# Deckelplatine_v092.net
KiCad netlist of a schematic drawn in EAGLE
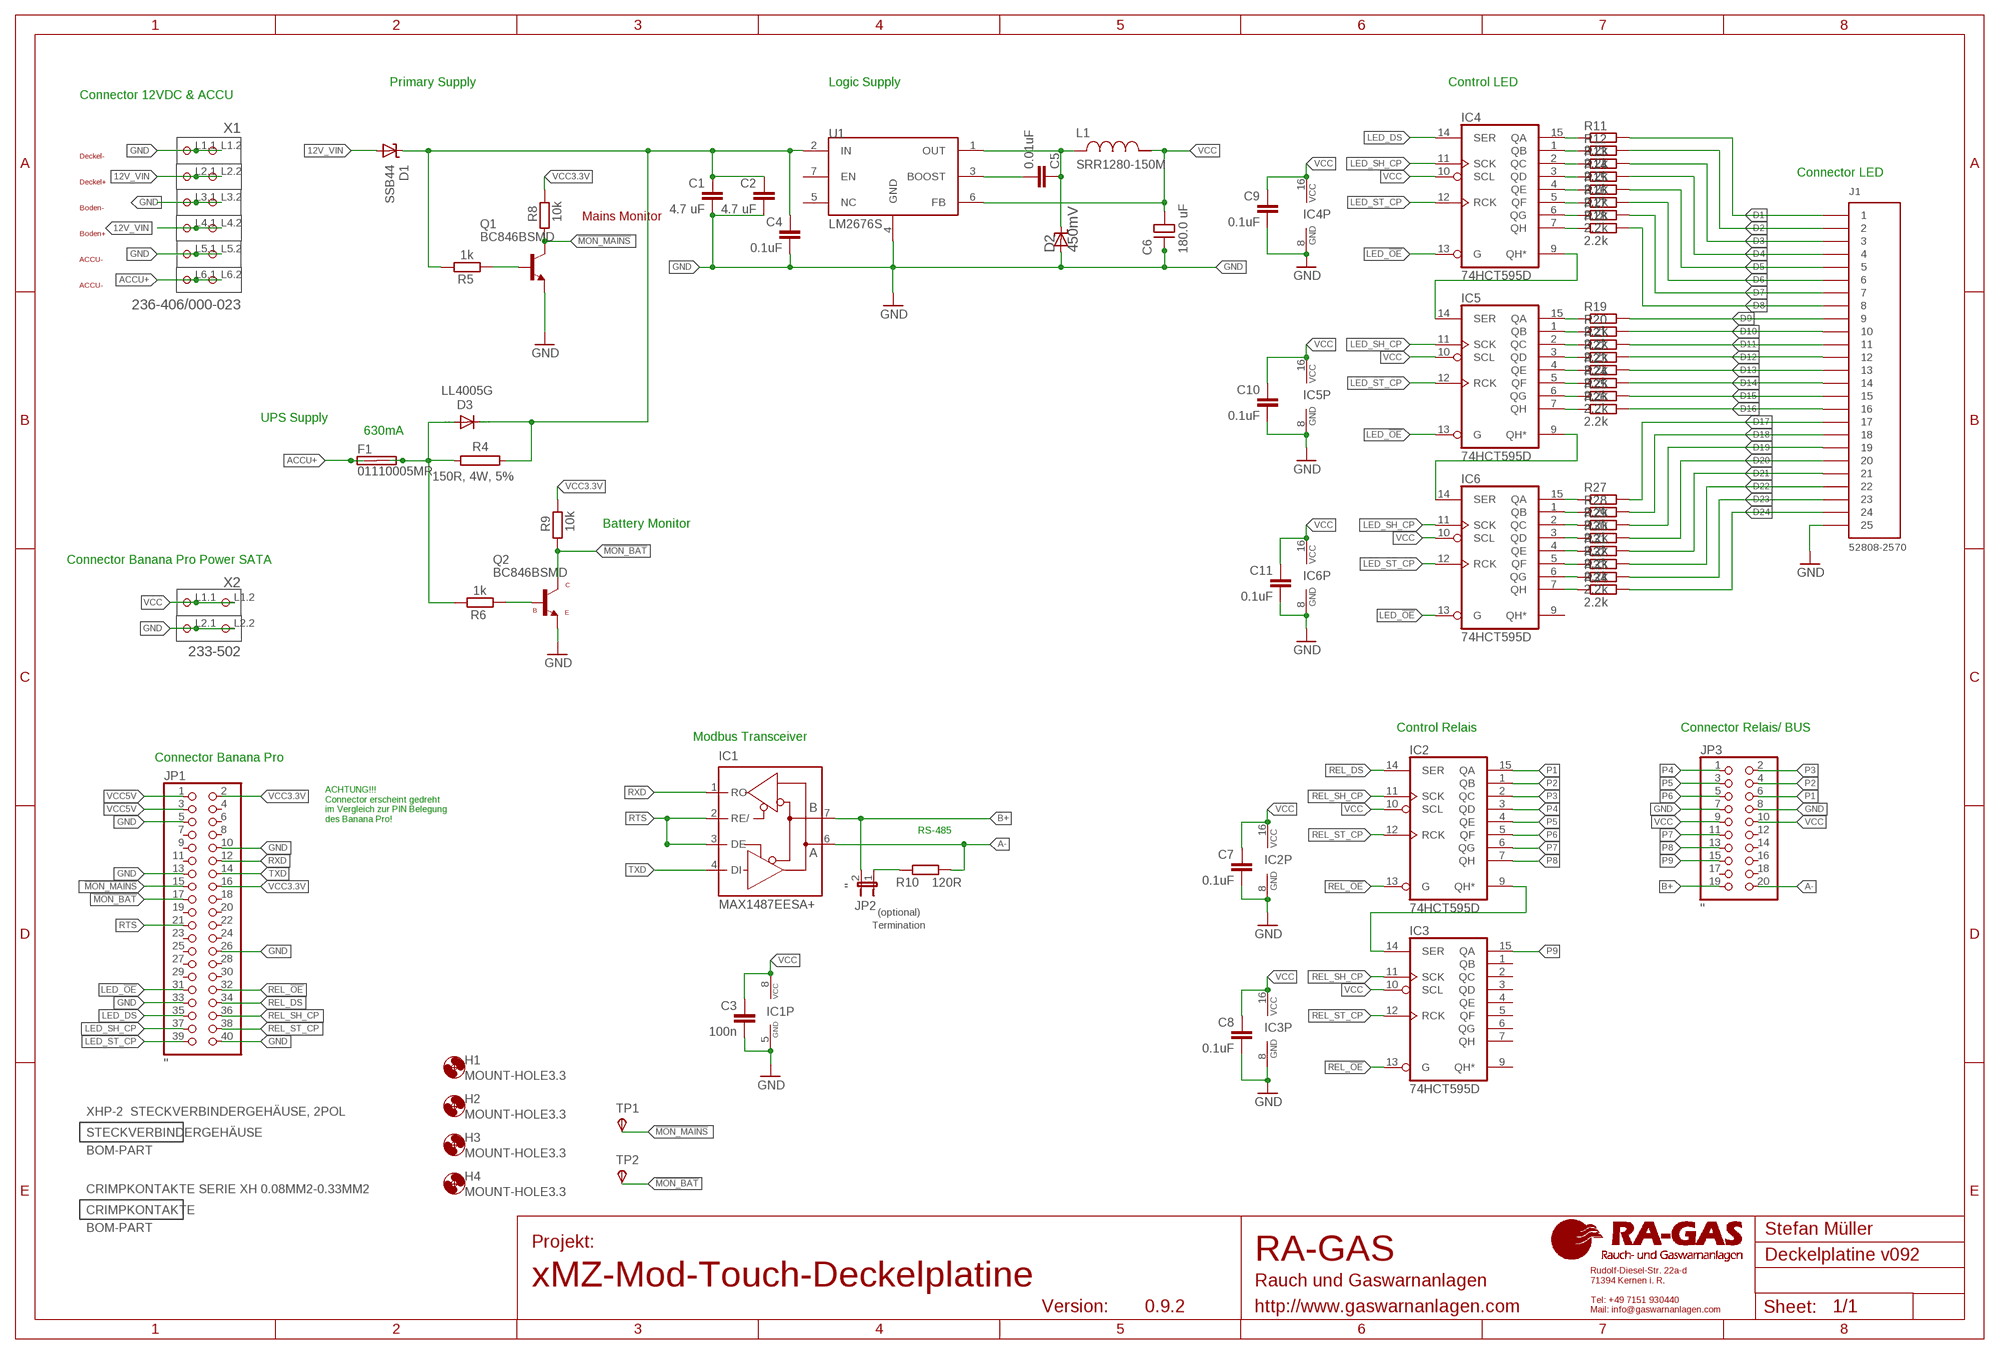
[diagram p0: schematic, sheet 1]

(export (version "E")
  (design (tool "Eeschema 10.0.6"))
  (components
    (comp (ref "C1")
      (value "4.7 uF")
      (footprint "eagle-import:GRM21BR61E475MA12L")
      (fields (field (name "MANUFACTURER_PART_NUMBER") "GRM21BR61E475MA12L") (field (name "MF") "MURATA"))
      (libsource (lib "eagle-import") (part "GRM21BR61E475MA12L"))
    )
    (comp (ref "C2")
      (value "4.7 uF")
      (footprint "eagle-import:GRM21BR61E475MA12L")
      (fields (field (name "MANUFACTURER_PART_NUMBER") "GRM21BR61E475MA12L") (field (name "MF") "MURATA"))
      (libsource (lib "eagle-import") (part "GRM21BR61E475MA12L"))
    )
    (comp (ref "C3")
      (value "100n")
      (footprint "eagle-import:C0603")
      (fields
        (field (name "MF") "KEMET")
        (field (name "MPN") "C0603C104K8RACTU")
        (field (name "PARTNO") "ECHU-16-100N")
      )
      (libsource (lib "eagle-import") (part "C-EUC0603"))
    )
    (comp (ref "C4")
      (value "0.1uF")
      (footprint "eagle-import:0805")
      (fields (field (name "MANUFACTURER_PART_NUMBER") "08053C104KAT2A") (field (name "MF") "AVX"))
      (libsource (lib "eagle-import") (part "08053C104KAT2A"))
    )
    (comp (ref "C5")
      (value "0.01uF")
      (footprint "eagle-import:GRM216R71H103KA01D")
      (fields (field (name "MANUFACTURER_PART_NUMBER") "GRM216R71H103KA01D") (field (name "MF") "MURATA"))
      (libsource (lib "eagle-import") (part "GRM216R71H103KA01D"))
    )
    (comp (ref "C6")
      (value "180.0 uF")
      (footprint "eagle-import:SM_RADIAL_10MM")
      (fields
        (field (name "MF") "PANASONIC ELECTRONIC COMPONENTS")
        (field (name "MPN") "16SVP180MX")
        (field (name "PARTNO") "RAD FC 560/35")
      )
      (libsource (lib "eagle-import") (part "16SVP180MSM_RADIAL_10MM"))
    )
    (comp (ref "C7")
      (value "0.1uF")
      (footprint "eagle-import:C0603")
      (fields
        (field (name "MF") "KEMET")
        (field (name "MPN") "C0603C104K8RACTU")
        (field (name "PARTNO") "SMD TAN.0,1/35")
      )
      (libsource (lib "eagle-import") (part "C-EUC0603"))
    )
    (comp (ref "C8")
      (value "0.1uF")
      (footprint "eagle-import:C0603")
      (fields
        (field (name "MF") "KEMET")
        (field (name "MPN") "C0603C104K8RACTU")
        (field (name "PARTNO") "SMD TAN.0,1/35")
      )
      (libsource (lib "eagle-import") (part "C-EUC0603"))
    )
    (comp (ref "C9")
      (value "0.1uF")
      (footprint "eagle-import:C0603")
      (fields
        (field (name "MF") "KEMET")
        (field (name "MPN") "C0603C104K8RACTU")
        (field (name "PARTNO") "SMD TAN.0,1/35")
      )
      (libsource (lib "eagle-import") (part "C-EUC0603"))
    )
    (comp (ref "C10")
      (value "0.1uF")
      (footprint "eagle-import:C0603")
      (fields
        (field (name "MF") "KEMET")
        (field (name "MPN") "C0603C104K8RACTU")
        (field (name "PARTNO") "SMD TAN.0,1/35")
      )
      (libsource (lib "eagle-import") (part "C-EUC0603"))
    )
    (comp (ref "C11")
      (value "0.1uF")
      (footprint "eagle-import:C0603")
      (fields
        (field (name "MF") "KEMET")
        (field (name "MPN") "C0603C104K8RACTU")
        (field (name "PARTNO") "SMD TAN.0,1/35")
      )
      (libsource (lib "eagle-import") (part "C-EUC0603"))
    )
    (comp (ref "D1")
      (value "SSB44")
      (footprint "eagle-import:SMBJ")
      (fields (field (name "MF") "VISHAY") (field (name "MPN") "SSB44-E3/52T"))
      (libsource (lib "eagle-import") (part "SUPPRESSOR-SMBJ"))
    )
    (comp (ref "D2")
      (value "450mV")
      (footprint "eagle-import:SMB")
      (fields (field (name "MANUFACTURER_PART_NUMBER") "B340LB-13-F") (field (name "MF") "DIODES INC."))
      (libsource (lib "eagle-import") (part "B340LB-13-F"))
    )
    (comp (ref "D3")
      (value "LL4005G")
      (footprint "eagle-import:MELF-MLL41")
      (fields (field (name "MF") "TAIWAN SEMICONDUCTOR"))
      (libsource (lib "eagle-import") (part "DIODE-MELF-MLL41"))
    )
    (comp (ref "F1")
      (value "01110005MR")
      (footprint "eagle-import:01110005MR")
      (fields (field (name "MF") "LITTELFUSE"))
      (libsource (lib "eagle-import") (part "01110005MR"))
    )
    (comp (ref "H1")
      (value "MOUNT-HOLE3.3")
      (footprint "eagle-import:3,3")
      (libsource (lib "eagle-import") (part "MOUNT-HOLE3.3"))
    )
    (comp (ref "H2")
      (value "MOUNT-HOLE3.3")
      (footprint "eagle-import:3,3")
      (libsource (lib "eagle-import") (part "MOUNT-HOLE3.3"))
    )
    (comp (ref "H3")
      (value "MOUNT-HOLE3.3")
      (footprint "eagle-import:3,3")
      (libsource (lib "eagle-import") (part "MOUNT-HOLE3.3"))
    )
    (comp (ref "H4")
      (value "MOUNT-HOLE3.3")
      (footprint "eagle-import:3,3")
      (libsource (lib "eagle-import") (part "MOUNT-HOLE3.3"))
    )
    (comp (ref "IC1")
      (value "MAX1487EESA+")
      (footprint "eagle-import:SO08")
      (fields
        (field (name "MF") "MAXIM")
        (field (name "MPN") "MAX481CSA")
        (field (name "MF_1") "MAXIM INTEGRATED PRODUCTS")
        (field (name "MPN_1") "MAX1487EESA+")
        (field (name "OC_FARNELL") "1593310")
        (field (name "PARTNO") "MAX481CSA")
      )
      (libsource (lib "eagle-import") (part "MAX481CSA"))
    )
    (comp (ref "IC2")
      (value "74HCT595D")
      (footprint "eagle-import:SO16")
      (fields
        (field (name "MF") "NXP")
        (field (name "MPN") "74HCT595D")
        (field (name "OC_FARNELL") "2098004")
        (field (name "PARTNO") "SMD HC 595")
      )
      (libsource (lib "eagle-import") (part "74595DHCT"))
    )
    (comp (ref "IC3")
      (value "74HCT595D")
      (footprint "eagle-import:SO16")
      (fields
        (field (name "MF") "NXP")
        (field (name "MPN") "74HCT595D")
        (field (name "OC_FARNELL") "2098004")
        (field (name "PARTNO") "SMD HC 595")
      )
      (libsource (lib "eagle-import") (part "74595DHCT"))
    )
    (comp (ref "IC4")
      (value "74HCT595D")
      (footprint "eagle-import:SO16")
      (fields
        (field (name "MF") "NXP")
        (field (name "MPN") "74HCT595D")
        (field (name "OC_FARNELL") "2098004")
        (field (name "PARTNO") "SMD HC 595")
      )
      (libsource (lib "eagle-import") (part "74595DHCT"))
    )
    (comp (ref "IC5")
      (value "74HCT595D")
      (footprint "eagle-import:SO16")
      (fields
        (field (name "MF") "NXP")
        (field (name "MPN") "74HCT595D")
        (field (name "OC_FARNELL") "2098004")
        (field (name "PARTNO") "SMD HC 595")
      )
      (libsource (lib "eagle-import") (part "74595DHCT"))
    )
    (comp (ref "IC6")
      (value "74HCT595D")
      (footprint "eagle-import:SO16")
      (fields
        (field (name "MF") "NXP")
        (field (name "MPN") "74HCT595D")
        (field (name "OC_FARNELL") "2098004")
        (field (name "PARTNO") "SMD HC 595")
      )
      (libsource (lib "eagle-import") (part "74595DHCT"))
    )
    (comp (ref "J1")
      (value "52808-2570")
      (footprint "eagle-import:52808-2570")
      (fields (field (name "MF") "MOLEX"))
      (libsource (lib "eagle-import") (part "52808-2570"))
    )
    (comp (ref "JP1")
      (value "''")
      (footprint "eagle-import:2X20")
      (fields (field (name "MF") "HARWIN") (field (name "MPN") "M20-6112045"))
      (libsource (lib "eagle-import") (part "PINHD-2X20"))
    )
    (comp (ref "JP2")
      (value "''")
      (footprint "eagle-import:JP1")
      (fields (field (name "MF") "TE CONNECTIVITY / AMP") (field (name "MPN") "825433-2"))
      (libsource (lib "eagle-import") (part "JP1E"))
    )
    (comp (ref "JP3")
      (value "''")
      (footprint "eagle-import:2X10")
      (fields (field (name "MF") "TE CONNECTIVITY / AMP") (field (name "MPN") "5103308-5"))
      (libsource (lib "eagle-import") (part "PINHD-2X10"))
    )
    (comp (ref "L1")
      (value "SRR1280-150M")
      (footprint "eagle-import:SRR1280")
      (fields (field (name "MF") "COILCRAFT") (field (name "MPN") "MSS1278-153MLD"))
      (libsource (lib "eagle-import") (part "SRR1280-150M"))
    )
    (comp (ref "Q1")
      (value "BC846BSMD")
      (footprint "eagle-import:SOT23")
      (fields (field (name "MF") "NXP") (field (name "MPN") "BC846,215"))
      (libsource (lib "eagle-import") (part "BC846SMDB"))
    )
    (comp (ref "Q2")
      (value "BC846BSMD")
      (footprint "eagle-import:SOT23")
      (fields (field (name "MF") "NXP") (field (name "MPN") "BC846,215"))
      (libsource (lib "eagle-import") (part "BC846SMDB"))
    )
    (comp (ref "R4")
      (value "150R, 4W, 5%")
      (footprint "eagle-import:KH206-8")
      (fields
        (field (name "MF") "TE CONNECTIVITY / CGS")
        (field (name "MPN") "ER74150RJT")
        (field (name "OC_FARNELL") "1751842")
      )
      (libsource (lib "eagle-import") (part "RKH206-8"))
    )
    (comp (ref "R5")
      (value "1k")
      (footprint "eagle-import:R1210")
      (fields (field (name "MF") "PANASONIC ELECTRONIC COMPONENTS") (field (name "MPN") "ERJP14F1001U"))
      (libsource (lib "eagle-import") (part "rcl_R-EU_R1210"))
    )
    (comp (ref "R6")
      (value "1k")
      (footprint "eagle-import:R1210")
      (fields (field (name "MF") "PANASONIC ELECTRONIC COMPONENTS") (field (name "MPN") "ERJP14F1001U"))
      (libsource (lib "eagle-import") (part "rcl_R-EU_R1210"))
    )
    (comp (ref "R8")
      (value "10k")
      (footprint "eagle-import:R1210")
      (fields (field (name "MF") "PANASONIC ELECTRONIC COMPONENTS") (field (name "MPN") "ERJP14F1002U"))
      (libsource (lib "eagle-import") (part "rcl_R-EU_R1210"))
    )
    (comp (ref "R9")
      (value "10k")
      (footprint "eagle-import:R1210")
      (fields (field (name "MF") "PANASONIC ELECTRONIC COMPONENTS") (field (name "MPN") "ERJP14F1002U"))
      (libsource (lib "eagle-import") (part "rcl_R-EU_R1210"))
    )
    (comp (ref "R10")
      (value "120R")
      (footprint "eagle-import:R1206")
      (fields (field (name "MF") "TE CONNECTIVITY") (field (name "MPN") "CRGH1206F120R"))
      (libsource (lib "eagle-import") (part "rcl_R-EU_R1206"))
    )
    (comp (ref "R11")
      (value "2.2k")
      (footprint "eagle-import:R0603")
      (fields
        (field (name "MF") "YAGEO (PHYCOMP)")
        (field (name "MPN") "RC0603FR-072K2L")
        (field (name "PARTNO") "SMD-0603 2,2K")
      )
      (libsource (lib "eagle-import") (part "R-EU_R0603"))
    )
    (comp (ref "R12")
      (value "2.2k")
      (footprint "eagle-import:R0603")
      (fields
        (field (name "MF") "YAGEO (PHYCOMP)")
        (field (name "MPN") "RC0603FR-072K2L")
        (field (name "PARTNO") "SMD-0603 2,2K")
      )
      (libsource (lib "eagle-import") (part "R-EU_R0603"))
    )
    (comp (ref "R13")
      (value "2.2k")
      (footprint "eagle-import:R0603")
      (fields
        (field (name "MF") "YAGEO (PHYCOMP)")
        (field (name "MPN") "RC0603FR-072K2L")
        (field (name "PARTNO") "SMD-0603 2,2K")
      )
      (libsource (lib "eagle-import") (part "R-EU_R0603"))
    )
    (comp (ref "R14")
      (value "2.2k")
      (footprint "eagle-import:R0603")
      (fields
        (field (name "MF") "YAGEO (PHYCOMP)")
        (field (name "MPN") "RC0603FR-072K2L")
        (field (name "PARTNO") "SMD-0603 2,2K")
      )
      (libsource (lib "eagle-import") (part "R-EU_R0603"))
    )
    (comp (ref "R15")
      (value "2.2k")
      (footprint "eagle-import:R0603")
      (fields
        (field (name "MF") "YAGEO (PHYCOMP)")
        (field (name "MPN") "RC0603FR-072K2L")
        (field (name "PARTNO") "SMD-0603 2,2K")
      )
      (libsource (lib "eagle-import") (part "R-EU_R0603"))
    )
    (comp (ref "R16")
      (value "2.2k")
      (footprint "eagle-import:R0603")
      (fields
        (field (name "MF") "YAGEO (PHYCOMP)")
        (field (name "MPN") "RC0603FR-072K2L")
        (field (name "PARTNO") "SMD-0603 2,2K")
      )
      (libsource (lib "eagle-import") (part "R-EU_R0603"))
    )
    (comp (ref "R17")
      (value "2.2k")
      (footprint "eagle-import:R0603")
      (fields
        (field (name "MF") "YAGEO (PHYCOMP)")
        (field (name "MPN") "RC0603FR-072K2L")
        (field (name "PARTNO") "SMD-0603 2,2K")
      )
      (libsource (lib "eagle-import") (part "R-EU_R0603"))
    )
    (comp (ref "R18")
      (value "2.2k")
      (footprint "eagle-import:R0603")
      (fields
        (field (name "MF") "YAGEO (PHYCOMP)")
        (field (name "MPN") "RC0603FR-072K2L")
        (field (name "PARTNO") "SMD-0603 2,2K")
      )
      (libsource (lib "eagle-import") (part "R-EU_R0603"))
    )
    (comp (ref "R19")
      (value "2.2k")
      (footprint "eagle-import:R0603")
      (fields
        (field (name "MF") "YAGEO (PHYCOMP)")
        (field (name "MPN") "RC0603FR-072K2L")
        (field (name "PARTNO") "SMD-0603 2,2K")
      )
      (libsource (lib "eagle-import") (part "R-EU_R0603"))
    )
    (comp (ref "R20")
      (value "2.2k")
      (footprint "eagle-import:R0603")
      (fields
        (field (name "MF") "YAGEO (PHYCOMP)")
        (field (name "MPN") "RC0603FR-072K2L")
        (field (name "PARTNO") "SMD-0603 2,2K")
      )
      (libsource (lib "eagle-import") (part "R-EU_R0603"))
    )
    (comp (ref "R21")
      (value "2.2k")
      (footprint "eagle-import:R0603")
      (fields
        (field (name "MF") "YAGEO (PHYCOMP)")
        (field (name "MPN") "RC0603FR-072K2L")
        (field (name "PARTNO") "SMD-0603 2,2K")
      )
      (libsource (lib "eagle-import") (part "R-EU_R0603"))
    )
    (comp (ref "R22")
      (value "2.2k")
      (footprint "eagle-import:R0603")
      (fields
        (field (name "MF") "YAGEO (PHYCOMP)")
        (field (name "MPN") "RC0603FR-072K2L")
        (field (name "PARTNO") "SMD-0603 2,2K")
      )
      (libsource (lib "eagle-import") (part "R-EU_R0603"))
    )
    (comp (ref "R23")
      (value "2.2k")
      (footprint "eagle-import:R0603")
      (fields
        (field (name "MF") "YAGEO (PHYCOMP)")
        (field (name "MPN") "RC0603FR-072K2L")
        (field (name "PARTNO") "SMD-0603 2,2K")
      )
      (libsource (lib "eagle-import") (part "R-EU_R0603"))
    )
    (comp (ref "R24")
      (value "2.2k")
      (footprint "eagle-import:R0603")
      (fields
        (field (name "MF") "YAGEO (PHYCOMP)")
        (field (name "MPN") "RC0603FR-072K2L")
        (field (name "PARTNO") "SMD-0603 2,2K")
      )
      (libsource (lib "eagle-import") (part "R-EU_R0603"))
    )
    (comp (ref "R25")
      (value "2.2k")
      (footprint "eagle-import:R0603")
      (fields
        (field (name "MF") "YAGEO (PHYCOMP)")
        (field (name "MPN") "RC0603FR-072K2L")
        (field (name "PARTNO") "SMD-0603 2,2K")
      )
      (libsource (lib "eagle-import") (part "R-EU_R0603"))
    )
    (comp (ref "R26")
      (value "2.2k")
      (footprint "eagle-import:R0603")
      (fields
        (field (name "MF") "YAGEO (PHYCOMP)")
        (field (name "MPN") "RC0603FR-072K2L")
        (field (name "PARTNO") "SMD-0603 2,2K")
      )
      (libsource (lib "eagle-import") (part "R-EU_R0603"))
    )
    (comp (ref "R27")
      (value "2.2k")
      (footprint "eagle-import:R0603")
      (fields
        (field (name "MF") "YAGEO (PHYCOMP)")
        (field (name "MPN") "RC0603FR-072K2L")
        (field (name "PARTNO") "SMD-0603 2,2K")
      )
      (libsource (lib "eagle-import") (part "R-EU_R0603"))
    )
    (comp (ref "R28")
      (value "2.2k")
      (footprint "eagle-import:R0603")
      (fields
        (field (name "MF") "YAGEO (PHYCOMP)")
        (field (name "MPN") "RC0603FR-072K2L")
        (field (name "PARTNO") "SMD-0603 2,2K")
      )
      (libsource (lib "eagle-import") (part "R-EU_R0603"))
    )
    (comp (ref "R29")
      (value "2.2k")
      (footprint "eagle-import:R0603")
      (fields
        (field (name "MF") "YAGEO (PHYCOMP)")
        (field (name "MPN") "RC0603FR-072K2L")
        (field (name "PARTNO") "SMD-0603 2,2K")
      )
      (libsource (lib "eagle-import") (part "R-EU_R0603"))
    )
    (comp (ref "R30")
      (value "2.2k")
      (footprint "eagle-import:R0603")
      (fields
        (field (name "MF") "YAGEO (PHYCOMP)")
        (field (name "MPN") "RC0603FR-072K2L")
        (field (name "PARTNO") "SMD-0603 2,2K")
      )
      (libsource (lib "eagle-import") (part "R-EU_R0603"))
    )
    (comp (ref "R31")
      (value "2.2k")
      (footprint "eagle-import:R0603")
      (fields
        (field (name "MF") "YAGEO (PHYCOMP)")
        (field (name "MPN") "RC0603FR-072K2L")
        (field (name "PARTNO") "SMD-0603 2,2K")
      )
      (libsource (lib "eagle-import") (part "R-EU_R0603"))
    )
    (comp (ref "R32")
      (value "2.2k")
      (footprint "eagle-import:R0603")
      (fields
        (field (name "MF") "YAGEO (PHYCOMP)")
        (field (name "MPN") "RC0603FR-072K2L")
        (field (name "PARTNO") "SMD-0603 2,2K")
      )
      (libsource (lib "eagle-import") (part "R-EU_R0603"))
    )
    (comp (ref "R33")
      (value "2.2k")
      (footprint "eagle-import:R0603")
      (fields
        (field (name "MF") "YAGEO (PHYCOMP)")
        (field (name "MPN") "RC0603FR-072K2L")
        (field (name "PARTNO") "SMD-0603 2,2K")
      )
      (libsource (lib "eagle-import") (part "R-EU_R0603"))
    )
    (comp (ref "R34")
      (value "2.2k")
      (footprint "eagle-import:R0603")
      (fields
        (field (name "MF") "YAGEO (PHYCOMP)")
        (field (name "MPN") "RC0603FR-072K2L")
        (field (name "PARTNO") "SMD-0603 2,2K")
      )
      (libsource (lib "eagle-import") (part "R-EU_R0603"))
    )
    (comp (ref "TP1")
      (value "TPSB1,27")
      (footprint "eagle-import:B1,27")
      (libsource (lib "eagle-import") (part "TPSB1,27"))
    )
    (comp (ref "TP2")
      (value "TPSB1,27")
      (footprint "eagle-import:B1,27")
      (libsource (lib "eagle-import") (part "TPSB1,27"))
    )
    (comp (ref "U1")
      (value "LM2676S")
      (footprint "eagle-import:TO-263-7")
      (fields (field (name "MF") "TEXAS INSTRUMENTS") (field (name "MPN") "LM2676S-5.0/NOPB"))
      (libsource (lib "eagle-import") (part "LM2676S"))
    )
    (comp (ref "X1")
      (value "236-406/000-023")
      (footprint "eagle-import:P-236-406")
      (fields (field (name "MF") "WAGO") (field (name "MPN") "236-406"))
      (libsource (lib "eagle-import") (part "236-406/000-023"))
    )
    (comp (ref "X2")
      (value "233-502")
      (footprint "eagle-import:P-233-502")
      (fields (field (name "MF") "WAGO") (field (name "MPN") "233-502."))
      (libsource (lib "eagle-import") (part "233-502"))
    )
  )
  (nets
    (net (code "1") (name "/LED_~{OE}") (class "Default")
      (node (ref "IC4") (pin "13") (pinfunction "G_13") (pintype "input"))
      (node (ref "IC5") (pin "13") (pinfunction "G_13") (pintype "input"))
      (node (ref "IC6") (pin "13") (pinfunction "G_13") (pintype "input"))
      (node (ref "JP1") (pin "31") (pinfunction "31_31") (pintype "passive"))
    )
    (net (code "2") (name "/REL_~{OE}") (class "Default")
      (node (ref "IC2") (pin "13") (pinfunction "G_13") (pintype "input"))
      (node (ref "IC3") (pin "13") (pinfunction "G_13") (pintype "input"))
      (node (ref "JP1") (pin "32") (pinfunction "32_32") (pintype "passive"))
    )
    (net (code "3") (name "/~{MON_BAT}") (class "Default")
      (node (ref "JP1") (pin "17") (pinfunction "17_17") (pintype "passive"))
      (node (ref "Q2") (pin "3") (pinfunction "C_3") (pintype "passive"))
      (node (ref "R9") (pin "1") (pinfunction "1_1") (pintype "passive"))
      (node (ref "TP2") (pin "TP") (pinfunction "PP_TP") (pintype "input"))
    )
    (net (code "4") (name "/~{MON_MAINS}") (class "Default")
      (node (ref "JP1") (pin "15") (pinfunction "15_15") (pintype "passive"))
      (node (ref "Q1") (pin "3") (pinfunction "C_3") (pintype "passive"))
      (node (ref "R8") (pin "1") (pinfunction "1_1") (pintype "passive"))
      (node (ref "TP1") (pin "TP") (pinfunction "PP_TP") (pintype "input"))
    )
    (net (code "5") (name "12V_VIN") (class "Default")
      (node (ref "C1") (pin "1") (pinfunction "1_1") (pintype "passive"))
      (node (ref "C2") (pin "1") (pinfunction "1_1") (pintype "passive"))
      (node (ref "C4") (pin "1") (pinfunction "1_1") (pintype "passive"))
      (node (ref "D1") (pin "A") (pinfunction "A_A") (pintype "passive"))
      (node (ref "D1") (pin "C") (pinfunction "C_C") (pintype "passive"))
      (node (ref "D3") (pin "C") (pinfunction "C_C") (pintype "passive"))
      (node (ref "R4") (pin "2") (pinfunction "2_2") (pintype "passive"))
      (node (ref "R5") (pin "2") (pinfunction "2_2") (pintype "passive"))
      (node (ref "U1") (pin "2") (pinfunction "IN_2") (pintype "power_in"))
      (node (ref "X1") (pin "L2.1") (pinfunction "P2.1_L2.1") (pintype "bidirectional"))
      (node (ref "X1") (pin "L2.2") (pinfunction "P2.2_L2.2") (pintype "bidirectional"))
      (node (ref "X1") (pin "L4.1") (pinfunction "P4.1_L4.1") (pintype "bidirectional"))
      (node (ref "X1") (pin "L4.2") (pinfunction "P4.2_L4.2") (pintype "bidirectional"))
    )
    (net (code "6") (name "A-") (class "Default")
      (node (ref "IC1") (pin "6") (pinfunction "A_6") (pintype "passive"))
      (node (ref "JP3") (pin "20") (pinfunction "20_20") (pintype "passive"))
      (node (ref "R10") (pin "2") (pinfunction "2_2") (pintype "passive"))
    )
    (net (code "7") (name "ACCU+") (class "Default")
      (node (ref "D3") (pin "A") (pinfunction "A_A") (pintype "passive"))
      (node (ref "F1") (pin "1A") (pinfunction "1A_1A") (pintype "passive"))
      (node (ref "F1") (pin "1B") (pinfunction "1B_1B") (pintype "passive"))
      (node (ref "F1") (pin "2A") (pinfunction "2A_2A") (pintype "passive"))
      (node (ref "F1") (pin "2B") (pinfunction "2B_2B") (pintype "passive"))
      (node (ref "R4") (pin "1") (pinfunction "1_1") (pintype "passive"))
      (node (ref "R6") (pin "2") (pinfunction "2_2") (pintype "passive"))
      (node (ref "X1") (pin "L6.1") (pinfunction "P6.1_L6.1") (pintype "bidirectional"))
      (node (ref "X1") (pin "L6.2") (pinfunction "P6.2_L6.2") (pintype "bidirectional"))
    )
    (net (code "8") (name "B+") (class "Default")
      (node (ref "IC1") (pin "7") (pinfunction "B_7") (pintype "passive"))
      (node (ref "JP2") (pin "2") (pinfunction "2_2") (pintype "passive"))
      (node (ref "JP3") (pin "19") (pinfunction "19_19") (pintype "passive"))
    )
    (net (code "9") (name "D1") (class "Default")
      (node (ref "J1") (pin "1") (pinfunction "1_1") (pintype "bidirectional"))
      (node (ref "R11") (pin "2") (pinfunction "2_2") (pintype "passive"))
    )
    (net (code "10") (name "D2") (class "Default")
      (node (ref "J1") (pin "2") (pinfunction "2_2") (pintype "bidirectional"))
      (node (ref "R12") (pin "2") (pinfunction "2_2") (pintype "passive"))
    )
    (net (code "11") (name "D3") (class "Default")
      (node (ref "J1") (pin "3") (pinfunction "3_3") (pintype "bidirectional"))
      (node (ref "R13") (pin "2") (pinfunction "2_2") (pintype "passive"))
    )
    (net (code "12") (name "D4") (class "Default")
      (node (ref "J1") (pin "4") (pinfunction "4_4") (pintype "bidirectional"))
      (node (ref "R14") (pin "2") (pinfunction "2_2") (pintype "passive"))
    )
    (net (code "13") (name "D5") (class "Default")
      (node (ref "J1") (pin "5") (pinfunction "5_5") (pintype "bidirectional"))
      (node (ref "R15") (pin "2") (pinfunction "2_2") (pintype "passive"))
    )
    (net (code "14") (name "D6") (class "Default")
      (node (ref "J1") (pin "6") (pinfunction "6_6") (pintype "bidirectional"))
      (node (ref "R16") (pin "2") (pinfunction "2_2") (pintype "passive"))
    )
    (net (code "15") (name "D7") (class "Default")
      (node (ref "J1") (pin "7") (pinfunction "7_7") (pintype "bidirectional"))
      (node (ref "R17") (pin "2") (pinfunction "2_2") (pintype "passive"))
    )
    (net (code "16") (name "D8") (class "Default")
      (node (ref "J1") (pin "8") (pinfunction "8_8") (pintype "bidirectional"))
      (node (ref "R18") (pin "2") (pinfunction "2_2") (pintype "passive"))
    )
    (net (code "17") (name "D9") (class "Default")
      (node (ref "J1") (pin "9") (pinfunction "9_9") (pintype "bidirectional"))
      (node (ref "R19") (pin "2") (pinfunction "2_2") (pintype "passive"))
    )
    (net (code "18") (name "D10") (class "Default")
      (node (ref "J1") (pin "10") (pinfunction "10_10") (pintype "bidirectional"))
      (node (ref "R20") (pin "2") (pinfunction "2_2") (pintype "passive"))
    )
    (net (code "19") (name "D11") (class "Default")
      (node (ref "J1") (pin "11") (pinfunction "11_11") (pintype "bidirectional"))
      (node (ref "R21") (pin "2") (pinfunction "2_2") (pintype "passive"))
    )
    (net (code "20") (name "D12") (class "Default")
      (node (ref "J1") (pin "12") (pinfunction "12_12") (pintype "bidirectional"))
      (node (ref "R22") (pin "2") (pinfunction "2_2") (pintype "passive"))
    )
    (net (code "21") (name "D13") (class "Default")
      (node (ref "J1") (pin "13") (pinfunction "13_13") (pintype "bidirectional"))
      (node (ref "R23") (pin "2") (pinfunction "2_2") (pintype "passive"))
    )
    (net (code "22") (name "D14") (class "Default")
      (node (ref "J1") (pin "14") (pinfunction "14_14") (pintype "bidirectional"))
      (node (ref "R24") (pin "2") (pinfunction "2_2") (pintype "passive"))
    )
    (net (code "23") (name "D15") (class "Default")
      (node (ref "J1") (pin "15") (pinfunction "15_15") (pintype "bidirectional"))
      (node (ref "R25") (pin "2") (pinfunction "2_2") (pintype "passive"))
    )
    (net (code "24") (name "D16") (class "Default")
      (node (ref "J1") (pin "16") (pinfunction "16_16") (pintype "bidirectional"))
      (node (ref "R26") (pin "2") (pinfunction "2_2") (pintype "passive"))
    )
    (net (code "25") (name "D17") (class "Default")
      (node (ref "J1") (pin "17") (pinfunction "17_17") (pintype "bidirectional"))
      (node (ref "R27") (pin "2") (pinfunction "2_2") (pintype "passive"))
    )
    (net (code "26") (name "D18") (class "Default")
      (node (ref "J1") (pin "18") (pinfunction "18_18") (pintype "bidirectional"))
      (node (ref "R28") (pin "2") (pinfunction "2_2") (pintype "passive"))
    )
    (net (code "27") (name "D19") (class "Default")
      (node (ref "J1") (pin "19") (pinfunction "19_19") (pintype "bidirectional"))
      (node (ref "R29") (pin "2") (pinfunction "2_2") (pintype "passive"))
    )
    (net (code "28") (name "D20") (class "Default")
      (node (ref "J1") (pin "20") (pinfunction "20_20") (pintype "bidirectional"))
      (node (ref "R30") (pin "2") (pinfunction "2_2") (pintype "passive"))
    )
    (net (code "29") (name "D21") (class "Default")
      (node (ref "J1") (pin "21") (pinfunction "21_21") (pintype "bidirectional"))
      (node (ref "R31") (pin "2") (pinfunction "2_2") (pintype "passive"))
    )
    (net (code "30") (name "D22") (class "Default")
      (node (ref "J1") (pin "22") (pinfunction "22_22") (pintype "bidirectional"))
      (node (ref "R32") (pin "2") (pinfunction "2_2") (pintype "passive"))
    )
    (net (code "31") (name "D23") (class "Default")
      (node (ref "J1") (pin "23") (pinfunction "23_23") (pintype "bidirectional"))
      (node (ref "R33") (pin "2") (pinfunction "2_2") (pintype "passive"))
    )
    (net (code "32") (name "D24") (class "Default")
      (node (ref "J1") (pin "24") (pinfunction "24_24") (pintype "bidirectional"))
      (node (ref "R34") (pin "2") (pinfunction "2_2") (pintype "passive"))
    )
    (net (code "33") (name "GND") (class "Default")
      (node (ref "C1") (pin "2") (pinfunction "2_2") (pintype "passive"))
      (node (ref "C10") (pin "2") (pinfunction "2_2") (pintype "passive"))
      (node (ref "C11") (pin "2") (pinfunction "2_2") (pintype "passive"))
      (node (ref "C2") (pin "2") (pinfunction "2_2") (pintype "passive"))
      (node (ref "C3") (pin "2") (pinfunction "2_2") (pintype "passive"))
      (node (ref "C4") (pin "2") (pinfunction "2_2") (pintype "passive"))
      (node (ref "C6") (pin "2") (pinfunction "-_2") (pintype "passive"))
      (node (ref "C7") (pin "2") (pinfunction "2_2") (pintype "passive"))
      (node (ref "C8") (pin "2") (pinfunction "2_2") (pintype "passive"))
      (node (ref "C9") (pin "2") (pinfunction "2_2") (pintype "passive"))
      (node (ref "D2") (pin "A") (pinfunction "A_A") (pintype "passive"))
      (node (ref "IC1") (pin "5") (pinfunction "GND_5") (pintype "power_in"))
      (node (ref "IC2") (pin "8") (pinfunction "GND_8") (pintype "power_in"))
      (node (ref "IC3") (pin "8") (pinfunction "GND_8") (pintype "power_in"))
      (node (ref "IC4") (pin "8") (pinfunction "GND_8") (pintype "power_in"))
      (node (ref "IC5") (pin "8") (pinfunction "GND_8") (pintype "power_in"))
      (node (ref "IC6") (pin "8") (pinfunction "GND_8") (pintype "power_in"))
      (node (ref "J1") (pin "25") (pinfunction "25_25") (pintype "bidirectional"))
      (node (ref "JP1") (pin "10") (pinfunction "10_10") (pintype "passive"))
      (node (ref "JP1") (pin "13") (pinfunction "13_13") (pintype "passive"))
      (node (ref "JP1") (pin "26") (pinfunction "26_26") (pintype "passive"))
      (node (ref "JP1") (pin "33") (pinfunction "33_33") (pintype "passive"))
      (node (ref "JP1") (pin "40") (pinfunction "40_40") (pintype "passive"))
      (node (ref "JP1") (pin "5") (pinfunction "5_5") (pintype "passive"))
      (node (ref "JP3") (pin "7") (pinfunction "7_7") (pintype "passive"))
      (node (ref "JP3") (pin "8") (pinfunction "8_8") (pintype "passive"))
      (node (ref "Q1") (pin "2") (pinfunction "E_2") (pintype "passive"))
      (node (ref "Q2") (pin "2") (pinfunction "E_2") (pintype "passive"))
      (node (ref "U1") (pin "4") (pinfunction "GND_4") (pintype "power_in"))
      (node (ref "X1") (pin "L1.1") (pinfunction "P1.1_L1.1") (pintype "bidirectional"))
      (node (ref "X1") (pin "L1.2") (pinfunction "P1.2_L1.2") (pintype "bidirectional"))
      (node (ref "X1") (pin "L3.1") (pinfunction "P3.1_L3.1") (pintype "bidirectional"))
      (node (ref "X1") (pin "L3.2") (pinfunction "P3.2_L3.2") (pintype "bidirectional"))
      (node (ref "X1") (pin "L5.1") (pinfunction "P5.1_L5.1") (pintype "bidirectional"))
      (node (ref "X1") (pin "L5.2") (pinfunction "P5.2_L5.2") (pintype "bidirectional"))
      (node (ref "X2") (pin "L2.1") (pinfunction "P2.1_L2.1") (pintype "bidirectional"))
      (node (ref "X2") (pin "L2.2") (pinfunction "P2.2_L2.2") (pintype "bidirectional"))
    )
    (net (code "34") (name "LED_DS") (class "Default")
      (node (ref "IC4") (pin "14") (pinfunction "SER_14") (pintype "input"))
      (node (ref "JP1") (pin "35") (pinfunction "35_35") (pintype "passive"))
    )
    (net (code "35") (name "LED_SH_CP") (class "Default")
      (node (ref "IC4") (pin "11") (pinfunction "SCK_11") (pintype "input"))
      (node (ref "IC5") (pin "11") (pinfunction "SCK_11") (pintype "input"))
      (node (ref "IC6") (pin "11") (pinfunction "SCK_11") (pintype "input"))
      (node (ref "JP1") (pin "37") (pinfunction "37_37") (pintype "passive"))
    )
    (net (code "36") (name "LED_ST_CP") (class "Default")
      (node (ref "IC4") (pin "12") (pinfunction "RCK_12") (pintype "input"))
      (node (ref "IC5") (pin "12") (pinfunction "RCK_12") (pintype "input"))
      (node (ref "IC6") (pin "12") (pinfunction "RCK_12") (pintype "input"))
      (node (ref "JP1") (pin "39") (pinfunction "39_39") (pintype "passive"))
    )
    (net (code "37") (name "Net-(IC2A-QH*)") (class "Default")
      (node (ref "IC2") (pin "9") (pinfunction "QH*_9") (pintype "tri_state"))
      (node (ref "IC3") (pin "14") (pinfunction "SER_14") (pintype "input"))
    )
    (net (code "38") (name "Net-(IC4A-QA)") (class "Default")
      (node (ref "IC4") (pin "15") (pinfunction "QA_15") (pintype "tri_state"))
      (node (ref "R11") (pin "1") (pinfunction "1_1") (pintype "passive"))
    )
    (net (code "39") (name "Net-(IC4A-QB)") (class "Default")
      (node (ref "IC4") (pin "1") (pinfunction "QB_1") (pintype "tri_state"))
      (node (ref "R12") (pin "1") (pinfunction "1_1") (pintype "passive"))
    )
    (net (code "40") (name "Net-(IC4A-QC)") (class "Default")
      (node (ref "IC4") (pin "2") (pinfunction "QC_2") (pintype "tri_state"))
      (node (ref "R13") (pin "1") (pinfunction "1_1") (pintype "passive"))
    )
    (net (code "41") (name "Net-(IC4A-QD)") (class "Default")
      (node (ref "IC4") (pin "3") (pinfunction "QD_3") (pintype "tri_state"))
      (node (ref "R14") (pin "1") (pinfunction "1_1") (pintype "passive"))
    )
    (net (code "42") (name "Net-(IC4A-QE)") (class "Default")
      (node (ref "IC4") (pin "4") (pinfunction "QE_4") (pintype "tri_state"))
      (node (ref "R15") (pin "1") (pinfunction "1_1") (pintype "passive"))
    )
    (net (code "43") (name "Net-(IC4A-QF)") (class "Default")
      (node (ref "IC4") (pin "5") (pinfunction "QF_5") (pintype "tri_state"))
      (node (ref "R16") (pin "1") (pinfunction "1_1") (pintype "passive"))
    )
    (net (code "44") (name "Net-(IC4A-QG)") (class "Default")
      (node (ref "IC4") (pin "6") (pinfunction "QG_6") (pintype "tri_state"))
      (node (ref "R17") (pin "1") (pinfunction "1_1") (pintype "passive"))
    )
    (net (code "45") (name "Net-(IC4A-QH)") (class "Default")
      (node (ref "IC4") (pin "7") (pinfunction "QH_7") (pintype "tri_state"))
      (node (ref "R18") (pin "1") (pinfunction "1_1") (pintype "passive"))
    )
    (net (code "46") (name "Net-(IC4A-QH*)") (class "Default")
      (node (ref "IC4") (pin "9") (pinfunction "QH*_9") (pintype "tri_state"))
      (node (ref "IC5") (pin "14") (pinfunction "SER_14") (pintype "input"))
    )
    (net (code "47") (name "Net-(IC5A-QA)") (class "Default")
      (node (ref "IC5") (pin "15") (pinfunction "QA_15") (pintype "tri_state"))
      (node (ref "R19") (pin "1") (pinfunction "1_1") (pintype "passive"))
    )
    (net (code "48") (name "Net-(IC5A-QB)") (class "Default")
      (node (ref "IC5") (pin "1") (pinfunction "QB_1") (pintype "tri_state"))
      (node (ref "R20") (pin "1") (pinfunction "1_1") (pintype "passive"))
    )
    (net (code "49") (name "Net-(IC5A-QC)") (class "Default")
      (node (ref "IC5") (pin "2") (pinfunction "QC_2") (pintype "tri_state"))
      (node (ref "R21") (pin "1") (pinfunction "1_1") (pintype "passive"))
    )
    (net (code "50") (name "Net-(IC5A-QD)") (class "Default")
      (node (ref "IC5") (pin "3") (pinfunction "QD_3") (pintype "tri_state"))
      (node (ref "R22") (pin "1") (pinfunction "1_1") (pintype "passive"))
    )
    (net (code "51") (name "Net-(IC5A-QE)") (class "Default")
      (node (ref "IC5") (pin "4") (pinfunction "QE_4") (pintype "tri_state"))
      (node (ref "R23") (pin "1") (pinfunction "1_1") (pintype "passive"))
    )
    (net (code "52") (name "Net-(IC5A-QF)") (class "Default")
      (node (ref "IC5") (pin "5") (pinfunction "QF_5") (pintype "tri_state"))
      (node (ref "R24") (pin "1") (pinfunction "1_1") (pintype "passive"))
    )
    (net (code "53") (name "Net-(IC5A-QG)") (class "Default")
      (node (ref "IC5") (pin "6") (pinfunction "QG_6") (pintype "tri_state"))
      (node (ref "R25") (pin "1") (pinfunction "1_1") (pintype "passive"))
    )
    (net (code "54") (name "Net-(IC5A-QH)") (class "Default")
      (node (ref "IC5") (pin "7") (pinfunction "QH_7") (pintype "tri_state"))
      (node (ref "R26") (pin "1") (pinfunction "1_1") (pintype "passive"))
    )
    (net (code "55") (name "Net-(IC5A-QH*)") (class "Default")
      (node (ref "IC5") (pin "9") (pinfunction "QH*_9") (pintype "tri_state"))
      (node (ref "IC6") (pin "14") (pinfunction "SER_14") (pintype "input"))
    )
    (net (code "56") (name "Net-(IC6A-QA)") (class "Default")
      (node (ref "IC6") (pin "15") (pinfunction "QA_15") (pintype "tri_state"))
      (node (ref "R27") (pin "1") (pinfunction "1_1") (pintype "passive"))
    )
    (net (code "57") (name "Net-(IC6A-QB)") (class "Default")
      (node (ref "IC6") (pin "1") (pinfunction "QB_1") (pintype "tri_state"))
      (node (ref "R28") (pin "1") (pinfunction "1_1") (pintype "passive"))
    )
    (net (code "58") (name "Net-(IC6A-QC)") (class "Default")
      (node (ref "IC6") (pin "2") (pinfunction "QC_2") (pintype "tri_state"))
      (node (ref "R29") (pin "1") (pinfunction "1_1") (pintype "passive"))
    )
    (net (code "59") (name "Net-(IC6A-QD)") (class "Default")
      (node (ref "IC6") (pin "3") (pinfunction "QD_3") (pintype "tri_state"))
      (node (ref "R30") (pin "1") (pinfunction "1_1") (pintype "passive"))
    )
    (net (code "60") (name "Net-(IC6A-QE)") (class "Default")
      (node (ref "IC6") (pin "4") (pinfunction "QE_4") (pintype "tri_state"))
      (node (ref "R31") (pin "1") (pinfunction "1_1") (pintype "passive"))
    )
    (net (code "61") (name "Net-(IC6A-QF)") (class "Default")
      (node (ref "IC6") (pin "5") (pinfunction "QF_5") (pintype "tri_state"))
      (node (ref "R32") (pin "1") (pinfunction "1_1") (pintype "passive"))
    )
    (net (code "62") (name "Net-(IC6A-QG)") (class "Default")
      (node (ref "IC6") (pin "6") (pinfunction "QG_6") (pintype "tri_state"))
      (node (ref "R33") (pin "1") (pinfunction "1_1") (pintype "passive"))
    )
    (net (code "63") (name "Net-(IC6A-QH)") (class "Default")
      (node (ref "IC6") (pin "7") (pinfunction "QH_7") (pintype "tri_state"))
      (node (ref "R34") (pin "1") (pinfunction "1_1") (pintype "passive"))
    )
    (net (code "64") (name "Net-(JP2-Pad1)") (class "Default")
      (node (ref "JP2") (pin "1") (pinfunction "1_1") (pintype "passive"))
      (node (ref "R10") (pin "1") (pinfunction "1_1") (pintype "passive"))
    )
    (net (code "65") (name "Net-(Q1-B)") (class "Default")
      (node (ref "Q1") (pin "1") (pinfunction "B_1") (pintype "passive"))
      (node (ref "R5") (pin "1") (pinfunction "1_1") (pintype "passive"))
    )
    (net (code "66") (name "Net-(Q2-B)") (class "Default")
      (node (ref "Q2") (pin "1") (pinfunction "B_1") (pintype "passive"))
      (node (ref "R6") (pin "1") (pinfunction "1_1") (pintype "passive"))
    )
    (net (code "67") (name "Net-(U1-BOOST)") (class "Default")
      (node (ref "C5") (pin "2") (pinfunction "2_2") (pintype "passive"))
      (node (ref "U1") (pin "3") (pinfunction "BOOST_3") (pintype "bidirectional"))
    )
    (net (code "68") (name "Net-(U1-OUT)") (class "Default")
      (node (ref "C5") (pin "1") (pinfunction "1_1") (pintype "passive"))
      (node (ref "D2") (pin "C") (pinfunction "C_C") (pintype "passive"))
      (node (ref "L1") (pin "1") (pinfunction "1_1") (pintype "passive"))
      (node (ref "U1") (pin "1") (pinfunction "OUT_1") (pintype "bidirectional"))
    )
    (net (code "69") (name "P1") (class "Default")
      (node (ref "IC2") (pin "15") (pinfunction "QA_15") (pintype "tri_state"))
      (node (ref "JP3") (pin "6") (pinfunction "6_6") (pintype "passive"))
    )
    (net (code "70") (name "P2") (class "Default")
      (node (ref "IC2") (pin "1") (pinfunction "QB_1") (pintype "tri_state"))
      (node (ref "JP3") (pin "4") (pinfunction "4_4") (pintype "passive"))
    )
    (net (code "71") (name "P3") (class "Default")
      (node (ref "IC2") (pin "2") (pinfunction "QC_2") (pintype "tri_state"))
      (node (ref "JP3") (pin "2") (pinfunction "2_2") (pintype "passive"))
    )
    (net (code "72") (name "P4") (class "Default")
      (node (ref "IC2") (pin "3") (pinfunction "QD_3") (pintype "tri_state"))
      (node (ref "JP3") (pin "1") (pinfunction "1_1") (pintype "passive"))
    )
    (net (code "73") (name "P5") (class "Default")
      (node (ref "IC2") (pin "4") (pinfunction "QE_4") (pintype "tri_state"))
      (node (ref "JP3") (pin "3") (pinfunction "3_3") (pintype "passive"))
    )
    (net (code "74") (name "P6") (class "Default")
      (node (ref "IC2") (pin "5") (pinfunction "QF_5") (pintype "tri_state"))
      (node (ref "JP3") (pin "5") (pinfunction "5_5") (pintype "passive"))
    )
    (net (code "75") (name "P7") (class "Default")
      (node (ref "IC2") (pin "6") (pinfunction "QG_6") (pintype "tri_state"))
      (node (ref "JP3") (pin "11") (pinfunction "11_11") (pintype "passive"))
    )
    (net (code "76") (name "P8") (class "Default")
      (node (ref "IC2") (pin "7") (pinfunction "QH_7") (pintype "tri_state"))
      (node (ref "JP3") (pin "13") (pinfunction "13_13") (pintype "passive"))
    )
    (net (code "77") (name "P9") (class "Default")
      (node (ref "IC3") (pin "15") (pinfunction "QA_15") (pintype "tri_state"))
      (node (ref "JP3") (pin "15") (pinfunction "15_15") (pintype "passive"))
    )
    (net (code "78") (name "REL_DS") (class "Default")
      (node (ref "IC2") (pin "14") (pinfunction "SER_14") (pintype "input"))
      (node (ref "JP1") (pin "34") (pinfunction "34_34") (pintype "passive"))
    )
    (net (code "79") (name "REL_SH_CP") (class "Default")
      (node (ref "IC2") (pin "11") (pinfunction "SCK_11") (pintype "input"))
      (node (ref "IC3") (pin "11") (pinfunction "SCK_11") (pintype "input"))
      (node (ref "JP1") (pin "36") (pinfunction "36_36") (pintype "passive"))
    )
    (net (code "80") (name "REL_ST_CP") (class "Default")
      (node (ref "IC2") (pin "12") (pinfunction "RCK_12") (pintype "input"))
      (node (ref "IC3") (pin "12") (pinfunction "RCK_12") (pintype "input"))
      (node (ref "JP1") (pin "38") (pinfunction "38_38") (pintype "passive"))
    )
    (net (code "81") (name "RTS") (class "Default")
      (node (ref "IC1") (pin "2") (pinfunction "RE/_2") (pintype "input"))
      (node (ref "IC1") (pin "3") (pinfunction "DE_3") (pintype "input"))
      (node (ref "JP1") (pin "21") (pinfunction "21_21") (pintype "passive"))
    )
    (net (code "82") (name "RXD") (class "Default")
      (node (ref "IC1") (pin "1") (pinfunction "RO_1") (pintype "output"))
      (node (ref "JP1") (pin "12") (pinfunction "12_12") (pintype "passive"))
    )
    (net (code "83") (name "TXD") (class "Default")
      (node (ref "IC1") (pin "4") (pinfunction "DI_4") (pintype "input"))
      (node (ref "JP1") (pin "14") (pinfunction "14_14") (pintype "passive"))
    )
    (net (code "84") (name "VCC") (class "Default")
      (node (ref "C10") (pin "1") (pinfunction "1_1") (pintype "passive"))
      (node (ref "C11") (pin "1") (pinfunction "1_1") (pintype "passive"))
      (node (ref "C3") (pin "1") (pinfunction "1_1") (pintype "passive"))
      (node (ref "C6") (pin "1") (pinfunction "+_1") (pintype "passive"))
      (node (ref "C7") (pin "1") (pinfunction "1_1") (pintype "passive"))
      (node (ref "C8") (pin "1") (pinfunction "1_1") (pintype "passive"))
      (node (ref "C9") (pin "1") (pinfunction "1_1") (pintype "passive"))
      (node (ref "IC1") (pin "8") (pinfunction "VCC_8") (pintype "power_in"))
      (node (ref "IC2") (pin "10") (pinfunction "SCL_10") (pintype "input"))
      (node (ref "IC2") (pin "16") (pinfunction "VCC_16") (pintype "power_in"))
      (node (ref "IC3") (pin "10") (pinfunction "SCL_10") (pintype "input"))
      (node (ref "IC3") (pin "16") (pinfunction "VCC_16") (pintype "power_in"))
      (node (ref "IC4") (pin "10") (pinfunction "SCL_10") (pintype "input"))
      (node (ref "IC4") (pin "16") (pinfunction "VCC_16") (pintype "power_in"))
      (node (ref "IC5") (pin "10") (pinfunction "SCL_10") (pintype "input"))
      (node (ref "IC5") (pin "16") (pinfunction "VCC_16") (pintype "power_in"))
      (node (ref "IC6") (pin "10") (pinfunction "SCL_10") (pintype "input"))
      (node (ref "IC6") (pin "16") (pinfunction "VCC_16") (pintype "power_in"))
      (node (ref "JP3") (pin "10") (pinfunction "10_10") (pintype "passive"))
      (node (ref "JP3") (pin "9") (pinfunction "9_9") (pintype "passive"))
      (node (ref "L1") (pin "2") (pinfunction "2_2") (pintype "passive"))
      (node (ref "U1") (pin "6") (pinfunction "FB_6") (pintype "bidirectional"))
      (node (ref "X2") (pin "L1.1") (pinfunction "P1.1_L1.1") (pintype "bidirectional"))
      (node (ref "X2") (pin "L1.2") (pinfunction "P1.2_L1.2") (pintype "bidirectional"))
    )
    (net (code "85") (name "VCC3.3V") (class "Default")
      (node (ref "JP1") (pin "16") (pinfunction "16_16") (pintype "passive"))
      (node (ref "JP1") (pin "2") (pinfunction "2_2") (pintype "passive"))
      (node (ref "R8") (pin "2") (pinfunction "2_2") (pintype "passive"))
      (node (ref "R9") (pin "2") (pinfunction "2_2") (pintype "passive"))
    )
    (net (code "86") (name "VCC5V") (class "Default")
      (node (ref "JP1") (pin "1") (pinfunction "1_1") (pintype "passive"))
      (node (ref "JP1") (pin "3") (pinfunction "3_3") (pintype "passive"))
    )
    (net (code "87") (name "unconnected-(IC3A-QB-Pad1)") (class "Default")
      (node (ref "IC3") (pin "1") (pinfunction "QB_1") (pintype "tri_state"))
    )
    (net (code "88") (name "unconnected-(IC3A-QC-Pad2)") (class "Default")
      (node (ref "IC3") (pin "2") (pinfunction "QC_2") (pintype "tri_state"))
    )
    (net (code "89") (name "unconnected-(IC3A-QD-Pad3)") (class "Default")
      (node (ref "IC3") (pin "3") (pinfunction "QD_3") (pintype "tri_state"))
    )
    (net (code "90") (name "unconnected-(IC3A-QE-Pad4)") (class "Default")
      (node (ref "IC3") (pin "4") (pinfunction "QE_4") (pintype "tri_state"))
    )
    (net (code "91") (name "unconnected-(IC3A-QF-Pad5)") (class "Default")
      (node (ref "IC3") (pin "5") (pinfunction "QF_5") (pintype "tri_state"))
    )
    (net (code "92") (name "unconnected-(IC3A-QG-Pad6)") (class "Default")
      (node (ref "IC3") (pin "6") (pinfunction "QG_6") (pintype "tri_state"))
    )
    (net (code "93") (name "unconnected-(IC3A-QH*-Pad9)") (class "Default")
      (node (ref "IC3") (pin "9") (pinfunction "QH*_9") (pintype "tri_state"))
    )
    (net (code "94") (name "unconnected-(IC3A-QH-Pad7)") (class "Default")
      (node (ref "IC3") (pin "7") (pinfunction "QH_7") (pintype "tri_state"))
    )
    (net (code "95") (name "unconnected-(IC6A-QH*-Pad9)") (class "Default")
      (node (ref "IC6") (pin "9") (pinfunction "QH*_9") (pintype "tri_state"))
    )
    (net (code "96") (name "unconnected-(JP1-Pad4)") (class "Default")
      (node (ref "JP1") (pin "4") (pinfunction "4_4") (pintype "passive"))
    )
    (net (code "97") (name "unconnected-(JP1-Pad6)") (class "Default")
      (node (ref "JP1") (pin "6") (pinfunction "6_6") (pintype "passive"))
    )
    (net (code "98") (name "unconnected-(JP1-Pad7)") (class "Default")
      (node (ref "JP1") (pin "7") (pinfunction "7_7") (pintype "passive"))
    )
    (net (code "99") (name "unconnected-(JP1-Pad8)") (class "Default")
      (node (ref "JP1") (pin "8") (pinfunction "8_8") (pintype "passive"))
    )
    (net (code "100") (name "unconnected-(JP1-Pad9)") (class "Default")
      (node (ref "JP1") (pin "9") (pinfunction "9_9") (pintype "passive"))
    )
    (net (code "101") (name "unconnected-(JP1-Pad11)") (class "Default")
      (node (ref "JP1") (pin "11") (pinfunction "11_11") (pintype "passive"))
    )
    (net (code "102") (name "unconnected-(JP1-Pad18)") (class "Default")
      (node (ref "JP1") (pin "18") (pinfunction "18_18") (pintype "passive"))
    )
    (net (code "103") (name "unconnected-(JP1-Pad19)") (class "Default")
      (node (ref "JP1") (pin "19") (pinfunction "19_19") (pintype "passive"))
    )
    (net (code "104") (name "unconnected-(JP1-Pad20)") (class "Default")
      (node (ref "JP1") (pin "20") (pinfunction "20_20") (pintype "passive"))
    )
    (net (code "105") (name "unconnected-(JP1-Pad22)") (class "Default")
      (node (ref "JP1") (pin "22") (pinfunction "22_22") (pintype "passive"))
    )
    (net (code "106") (name "unconnected-(JP1-Pad23)") (class "Default")
      (node (ref "JP1") (pin "23") (pinfunction "23_23") (pintype "passive"))
    )
    (net (code "107") (name "unconnected-(JP1-Pad24)") (class "Default")
      (node (ref "JP1") (pin "24") (pinfunction "24_24") (pintype "passive"))
    )
    (net (code "108") (name "unconnected-(JP1-Pad25)") (class "Default")
      (node (ref "JP1") (pin "25") (pinfunction "25_25") (pintype "passive"))
    )
    (net (code "109") (name "unconnected-(JP1-Pad27)") (class "Default")
      (node (ref "JP1") (pin "27") (pinfunction "27_27") (pintype "passive"))
    )
    (net (code "110") (name "unconnected-(JP1-Pad28)") (class "Default")
      (node (ref "JP1") (pin "28") (pinfunction "28_28") (pintype "passive"))
    )
    (net (code "111") (name "unconnected-(JP1-Pad29)") (class "Default")
      (node (ref "JP1") (pin "29") (pinfunction "29_29") (pintype "passive"))
    )
    (net (code "112") (name "unconnected-(JP1-Pad30)") (class "Default")
      (node (ref "JP1") (pin "30") (pinfunction "30_30") (pintype "passive"))
    )
    (net (code "113") (name "unconnected-(JP3-Pad12)") (class "Default")
      (node (ref "JP3") (pin "12") (pinfunction "12_12") (pintype "passive"))
    )
    (net (code "114") (name "unconnected-(JP3-Pad14)") (class "Default")
      (node (ref "JP3") (pin "14") (pinfunction "14_14") (pintype "passive"))
    )
    (net (code "115") (name "unconnected-(JP3-Pad16)") (class "Default")
      (node (ref "JP3") (pin "16") (pinfunction "16_16") (pintype "passive"))
    )
    (net (code "116") (name "unconnected-(JP3-Pad17)") (class "Default")
      (node (ref "JP3") (pin "17") (pinfunction "17_17") (pintype "passive"))
    )
    (net (code "117") (name "unconnected-(JP3-Pad18)") (class "Default")
      (node (ref "JP3") (pin "18") (pinfunction "18_18") (pintype "passive"))
    )
    (net (code "118") (name "unconnected-(U1-EN-Pad7)") (class "Default")
      (node (ref "U1") (pin "7") (pinfunction "EN_7") (pintype "bidirectional"))
    )
    (net (code "119") (name "unconnected-(U1-NC-Pad5)") (class "Default")
      (node (ref "U1") (pin "5") (pinfunction "NC_5") (pintype "no_connect"))
    )
  )
)
